# Shkaff.net
KiCad netlist of a schematic drawn in EAGLE
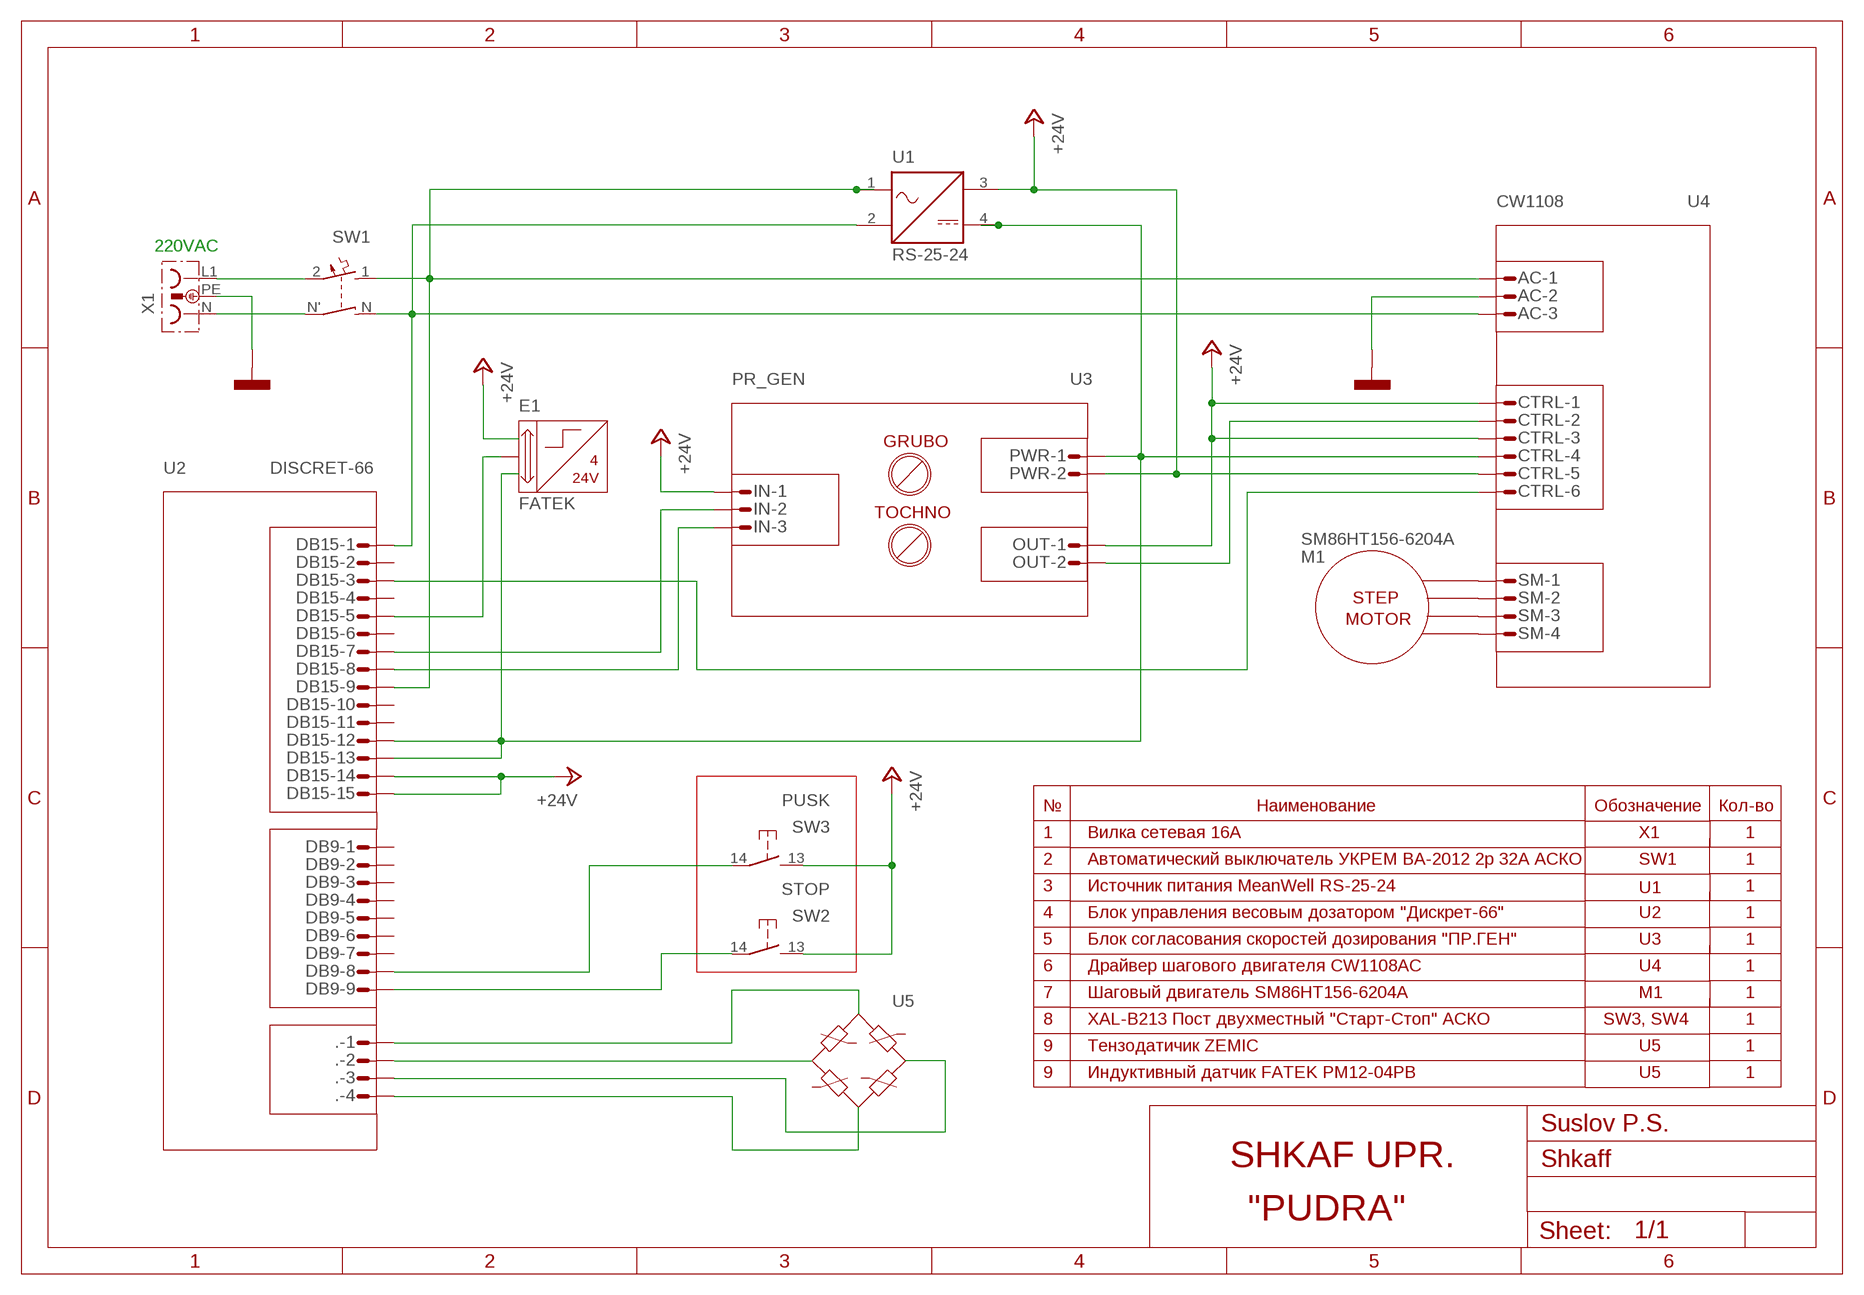
[diagram p0: schematic, sheet 1]

(export (version "E")
  (design (tool "Eeschema 10.0.6"))
  (components
    (comp (ref ".")
      (value "L04P")
      (footprint "eagle-import:L04P")
      (libsource (lib "eagle-import") (part "L04P"))
    )
    (comp (ref "AC")
      (value "L04P")
      (footprint "eagle-import:L04P")
      (libsource (lib "eagle-import") (part "L04P"))
    )
    (comp (ref "CTRL")
      (value "L09P")
      (footprint "eagle-import:L09P")
      (libsource (lib "eagle-import") (part "L09P"))
    )
    (comp (ref "DB9")
      (value "L09P")
      (footprint "eagle-import:L09P")
      (libsource (lib "eagle-import") (part "L09P"))
    )
    (comp (ref "DB15")
      (value "L15P")
      (footprint "eagle-import:L15P")
      (libsource (lib "eagle-import") (part "L15P"))
    )
    (comp (ref "E1")
      (value "FATEK")
      (footprint "eagle-import:6158EB")
      (libsource (lib "eagle-import") (part "6158EB"))
    )
    (comp (ref "IN")
      (value "L04P")
      (footprint "eagle-import:L04P")
      (libsource (lib "eagle-import") (part "L04P"))
    )
    (comp (ref "OUT")
      (value "L04P")
      (footprint "eagle-import:L04P")
      (libsource (lib "eagle-import") (part "L04P"))
    )
    (comp (ref "PWR")
      (value "L04P")
      (footprint "eagle-import:L04P")
      (libsource (lib "eagle-import") (part "L04P"))
    )
    (comp (ref "SM")
      (value "L04P")
      (footprint "eagle-import:L04P")
      (libsource (lib "eagle-import") (part "L04P"))
    )
    (comp (ref "SW1")
      (value "LEITUNGSSCHUTZSCHALTER_2-POL")
      (footprint "eagle-import:LEITUNGSSCHUTZSCHALTER_2-POL")
      (libsource (lib "eagle-import") (part "LEITUNGSSCHUTZSCHALTER_2-POL"))
    )
    (comp (ref "SW2")
      (value "STOP")
      (footprint "eagle-import:SCHLIESSER_TASTSCHALTER")
      (libsource (lib "eagle-import") (part "SCHLIESSER_TASTSCHALTER"))
    )
    (comp (ref "SW3")
      (value "PUSK")
      (footprint "eagle-import:SCHLIESSER_TASTSCHALTER")
      (libsource (lib "eagle-import") (part "SCHLIESSER_TASTSCHALTER"))
    )
    (comp (ref "U1")
      (value "RS-25-24")
      (footprint "eagle-import:NETZTEIL_GLEICHSPANNUNG")
      (libsource (lib "eagle-import") (part "NETZTEIL_GLEICHSPANNUNG"))
    )
    (comp (ref "X1")
      (value "STECKDOSE")
      (footprint "eagle-import:STECKDOSE")
      (libsource (lib "eagle-import") (part "STECKDOSE"))
    )
    (comp (ref "X2")
      (value "MASSE_ALLGEMEIN")
      (footprint "eagle-import:MASSE_ALLGEMEIN")
      (libsource (lib "eagle-import") (part "MASSE_ALLGEMEIN"))
    )
    (comp (ref "X6")
      (value "MASSE_ALLGEMEIN")
      (footprint "eagle-import:MASSE_ALLGEMEIN")
      (libsource (lib "eagle-import") (part "MASSE_ALLGEMEIN"))
    )
  )
  (nets
    (net (code "1") (name "+24V") (class "Default")
      (node (ref "CTRL") (pin "1") (pinfunction "S_1") (pintype "passive"))
      (node (ref "CTRL") (pin "3") (pinfunction "S_3") (pintype "passive"))
      (node (ref "CTRL") (pin "5") (pinfunction "S_5") (pintype "passive"))
      (node (ref "DB15") (pin "14") (pinfunction "S_14") (pintype "passive"))
      (node (ref "DB15") (pin "15") (pinfunction "S_15") (pintype "passive"))
      (node (ref "IN") (pin "1") (pinfunction "S_1") (pintype "passive"))
      (node (ref "OUT") (pin "1") (pinfunction "S_1") (pintype "passive"))
      (node (ref "PWR") (pin "2") (pinfunction "S_2") (pintype "passive"))
      (node (ref "SW2") (pin "13") (pinfunction "3_13") (pintype "input"))
      (node (ref "SW3") (pin "13") (pinfunction "3_13") (pintype "input"))
      (node (ref "U1") (pin "3") (pinfunction "3_3") (pintype "passive"))
    )
    (net (code "2") (name "Net-(ACA-S)") (class "Default")
      (node (ref "AC") (pin "1") (pinfunction "S_1") (pintype "passive"))
      (node (ref "DB15") (pin "9") (pinfunction "S_9") (pintype "passive"))
      (node (ref "SW1") (pin "1") (pinfunction "1_1") (pintype "passive"))
      (node (ref "U1") (pin "1") (pinfunction "1_1") (pintype "passive"))
    )
    (net (code "3") (name "Net-(ACB-S)") (class "Default")
      (node (ref "AC") (pin "2") (pinfunction "S_2") (pintype "passive"))
      (node (ref "X2") (pin "1") (pinfunction "0V_1") (pintype "passive"))
    )
    (net (code "4") (name "Net-(ACC-S)") (class "Default")
      (node (ref "AC") (pin "3") (pinfunction "S_3") (pintype "passive"))
      (node (ref "DB15") (pin "1") (pinfunction "S_1") (pintype "passive"))
      (node (ref "SW1") (pin "N") (pinfunction "N_N") (pintype "passive"))
      (node (ref "U1") (pin "2") (pinfunction "2_2") (pintype "passive"))
    )
    (net (code "5") (name "Net-(CTRLB-S)") (class "Default")
      (node (ref "CTRL") (pin "2") (pinfunction "S_2") (pintype "passive"))
      (node (ref "OUT") (pin "2") (pinfunction "S_2") (pintype "passive"))
    )
    (net (code "6") (name "Net-(CTRLD-S)") (class "Default")
      (node (ref "CTRL") (pin "4") (pinfunction "S_4") (pintype "passive"))
      (node (ref "DB15") (pin "12") (pinfunction "S_12") (pintype "passive"))
      (node (ref "DB15") (pin "13") (pinfunction "S_13") (pintype "passive"))
      (node (ref "PWR") (pin "1") (pinfunction "S_1") (pintype "passive"))
      (node (ref "U1") (pin "4") (pinfunction "4_4") (pintype "passive"))
    )
    (net (code "7") (name "Net-(CTRLF-S)") (class "Default")
      (node (ref "CTRL") (pin "6") (pinfunction "S_6") (pintype "passive"))
      (node (ref "DB15") (pin "3") (pinfunction "S_3") (pintype "passive"))
    )
    (net (code "8") (name "Net-(DB9H-S)") (class "Default")
      (node (ref "DB9") (pin "8") (pinfunction "S_8") (pintype "passive"))
      (node (ref "SW3") (pin "14") (pinfunction "4_14") (pintype "input"))
    )
    (net (code "9") (name "Net-(DB9I-S)") (class "Default")
      (node (ref "DB9") (pin "9") (pinfunction "S_9") (pintype "passive"))
      (node (ref "SW2") (pin "14") (pinfunction "4_14") (pintype "input"))
    )
    (net (code "10") (name "Net-(DB15K-S)") (class "Default")
      (node (ref "DB15") (pin "5") (pinfunction "S_5") (pintype "passive"))
      (node (ref "E1") (pin "1") (pinfunction "1_1") (pintype "passive"))
    )
    (net (code "11") (name "Net-(DB15M-S)") (class "Default")
      (node (ref "DB15") (pin "7") (pinfunction "S_7") (pintype "passive"))
      (node (ref "IN") (pin "2") (pinfunction "S_2") (pintype "passive"))
    )
    (net (code "12") (name "Net-(DB15N-S)") (class "Default")
      (node (ref "DB15") (pin "8") (pinfunction "S_8") (pintype "passive"))
      (node (ref "IN") (pin "3") (pinfunction "S_3") (pintype "passive"))
    )
    (net (code "13") (name "Net-(SW1-N-PadN')") (class "Default")
      (node (ref "SW1") (pin "N'") (pinfunction "N_N'") (pintype "passive"))
      (node (ref "X1") (pin "N") (pinfunction "N_N") (pintype "passive"))
    )
    (net (code "14") (name "Net-(SW1-Pad2)") (class "Default")
      (node (ref "SW1") (pin "2") (pinfunction "2_2") (pintype "passive"))
      (node (ref "X1") (pin "L1") (pinfunction "L1_L1") (pintype "passive"))
    )
    (net (code "15") (name "Net-(X6-0V)") (class "Default")
      (node (ref "X1") (pin "PE") (pinfunction "PE_PE") (pintype "passive"))
      (node (ref "X6") (pin "1") (pinfunction "0V_1") (pintype "passive"))
    )
    (net (code "16") (name "unconnected-(.A-S-Pad1)") (class "Default")
      (node (ref ".") (pin "1") (pinfunction "S_1") (pintype "passive"))
    )
    (net (code "17") (name "unconnected-(.B-S-Pad2)") (class "Default")
      (node (ref ".") (pin "2") (pinfunction "S_2") (pintype "passive"))
    )
    (net (code "18") (name "unconnected-(.C-S-Pad3)") (class "Default")
      (node (ref ".") (pin "3") (pinfunction "S_3") (pintype "passive"))
    )
    (net (code "19") (name "unconnected-(.D-S-Pad4)") (class "Default")
      (node (ref ".") (pin "4") (pinfunction "S_4") (pintype "passive"))
    )
    (net (code "20") (name "unconnected-(DB9A-S-Pad1)") (class "Default")
      (node (ref "DB9") (pin "1") (pinfunction "S_1") (pintype "passive"))
    )
    (net (code "21") (name "unconnected-(DB9B-S-Pad2)") (class "Default")
      (node (ref "DB9") (pin "2") (pinfunction "S_2") (pintype "passive"))
    )
    (net (code "22") (name "unconnected-(DB9C-S-Pad3)") (class "Default")
      (node (ref "DB9") (pin "3") (pinfunction "S_3") (pintype "passive"))
    )
    (net (code "23") (name "unconnected-(DB9D-S-Pad4)") (class "Default")
      (node (ref "DB9") (pin "4") (pinfunction "S_4") (pintype "passive"))
    )
    (net (code "24") (name "unconnected-(DB9E-S-Pad5)") (class "Default")
      (node (ref "DB9") (pin "5") (pinfunction "S_5") (pintype "passive"))
    )
    (net (code "25") (name "unconnected-(DB9F-S-Pad6)") (class "Default")
      (node (ref "DB9") (pin "6") (pinfunction "S_6") (pintype "passive"))
    )
    (net (code "26") (name "unconnected-(DB9G-S-Pad7)") (class "Default")
      (node (ref "DB9") (pin "7") (pinfunction "S_7") (pintype "passive"))
    )
    (net (code "27") (name "unconnected-(DB15B-S-Pad10)") (class "Default")
      (node (ref "DB15") (pin "10") (pinfunction "S_10") (pintype "passive"))
    )
    (net (code "28") (name "unconnected-(DB15C-S-Pad11)") (class "Default")
      (node (ref "DB15") (pin "11") (pinfunction "S_11") (pintype "passive"))
    )
    (net (code "29") (name "unconnected-(DB15H-S-Pad2)") (class "Default")
      (node (ref "DB15") (pin "2") (pinfunction "S_2") (pintype "passive"))
    )
    (net (code "30") (name "unconnected-(DB15J-S-Pad4)") (class "Default")
      (node (ref "DB15") (pin "4") (pinfunction "S_4") (pintype "passive"))
    )
    (net (code "31") (name "unconnected-(DB15L-S-Pad6)") (class "Default")
      (node (ref "DB15") (pin "6") (pinfunction "S_6") (pintype "passive"))
    )
    (net (code "32") (name "unconnected-(SMA-S-Pad1)") (class "Default")
      (node (ref "SM") (pin "1") (pinfunction "S_1") (pintype "passive"))
    )
    (net (code "33") (name "unconnected-(SMB-S-Pad2)") (class "Default")
      (node (ref "SM") (pin "2") (pinfunction "S_2") (pintype "passive"))
    )
    (net (code "34") (name "unconnected-(SMC-S-Pad3)") (class "Default")
      (node (ref "SM") (pin "3") (pinfunction "S_3") (pintype "passive"))
    )
    (net (code "35") (name "unconnected-(SMD-S-Pad4)") (class "Default")
      (node (ref "SM") (pin "4") (pinfunction "S_4") (pintype "passive"))
    )
  )
)
